# clock_src.net
KiCad netlist of a schematic drawn in EAGLE
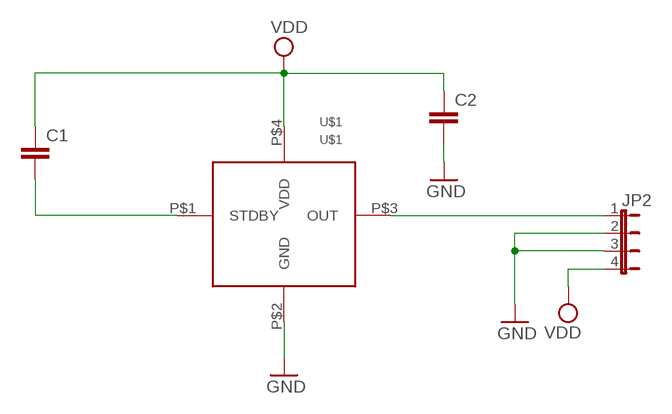
[diagram p0: schematic, sheet 1]

(export (version "E")
  (design (tool "Eeschema 10.0.6"))
  (components
    (comp (ref "C1")
      (value "C-EUC0603")
      (footprint "eagle-import:C0603")
      (libsource (lib "eagle-import") (part "C-EUC0603"))
    )
    (comp (ref "C2")
      (value "C-EUC0603")
      (footprint "eagle-import:C0603")
      (libsource (lib "eagle-import") (part "C-EUC0603"))
    )
    (comp (ref "JP2")
      (value "JP4E")
      (footprint "eagle-import:JP4")
      (libsource (lib "eagle-import") (part "JP4E"))
    )
    (comp (ref "U$1")
      (value "ASFLMB-24525")
      (footprint "eagle-import:ASFLMB-24525")
      (libsource (lib "eagle-import") (part "ASFLMB-24525"))
    )
  )
  (nets
    (net (code "1") (name "GND") (class "Default")
      (node (ref "C2") (pin "2") (pinfunction "2_2") (pintype "passive"))
      (node (ref "JP2") (pin "2") (pinfunction "2_2") (pintype "passive"))
      (node (ref "JP2") (pin "3") (pinfunction "3_3") (pintype "passive"))
      (node (ref "U$1") (pin "P$2") (pinfunction "GND_P$2") (pintype "bidirectional"))
    )
    (net (code "2") (name "Net-(U$1-OUT)") (class "Default")
      (node (ref "JP2") (pin "1") (pinfunction "1_1") (pintype "passive"))
      (node (ref "U$1") (pin "P$3") (pinfunction "OUT_P$3") (pintype "bidirectional"))
    )
    (net (code "3") (name "Net-(U$1-STDBY)") (class "Default")
      (node (ref "C1") (pin "2") (pinfunction "2_2") (pintype "passive"))
      (node (ref "U$1") (pin "P$1") (pinfunction "STDBY_P$1") (pintype "bidirectional"))
    )
    (net (code "4") (name "VDD") (class "Default")
      (node (ref "C1") (pin "1") (pinfunction "1_1") (pintype "passive"))
      (node (ref "C2") (pin "1") (pinfunction "1_1") (pintype "passive"))
      (node (ref "JP2") (pin "4") (pinfunction "4_4") (pintype "passive"))
      (node (ref "U$1") (pin "P$4") (pinfunction "VDD_P$4") (pintype "bidirectional"))
    )
  )
)
